# PCB.net
KiCad netlist of a schematic drawn in Altium Designer
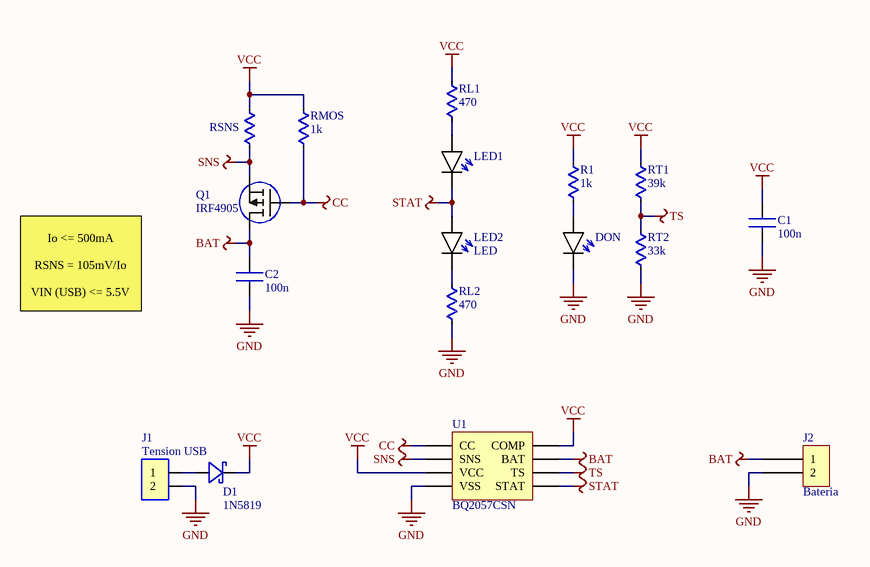
[diagram p0: PCB.SchDoc]

(export (version "E")
  (design (tool "Eeschema 10.0.6"))
  (components
    (comp (ref "C1")
      (value "100n")
      (footprint "CAP-CER")
      (fields (field (name "Comment") "CAP-CER"))
      (libsource (lib "AltiumLibrary") (part "CAP-CER"))
    )
    (comp (ref "C2")
      (value "100n")
      (footprint "CAP-CER")
      (fields (field (name "Comment") "CAP-CER"))
      (libsource (lib "AltiumLibrary") (part "CAP-CER"))
    )
    (comp (ref "D1") (value "1N5819") (footprint "DO-41") (libsource (lib "AltiumLibrary") (part "SCHOTTKY")))
    (comp (ref "DON") (value "LED") (footprint "LED-3MM-RED") (libsource (lib "AltiumLibrary") (part "LED")))
    (comp (ref "J1")
      (value "Tension USB")
      (footprint "BLOCK_TERMINAL-2")
      (libsource (lib "AltiumLibrary") (part "2-BLOCK_TERMINAL"))
    )
    (comp (ref "J2")
      (value "Bateria")
      (footprint "HEADER 1x2")
      (libsource (lib "AltiumLibrary") (part "Header 1x2"))
    )
    (comp (ref "LED1")
      (value "LED")
      (footprint "LED-3MM-GREEN")
      (libsource (lib "AltiumLibrary") (part "LED"))
    )
    (comp (ref "LED2") (value "LED") (footprint "LED-3MM-RED") (libsource (lib "AltiumLibrary") (part "LED")))
    (comp (ref "Q1")
      (value "IRF4905")
      (footprint "TO-220")
      (libsource (lib "AltiumLibrary") (part "P-MOSFET"))
    )
    (comp (ref "R1")
      (value "1k")
      (footprint "RES VERTICAL")
      (fields (field (name "Comment") "RES"))
      (libsource (lib "") (part "RES_1"))
    )
    (comp (ref "RL1")
      (value "470")
      (footprint "AXIAL-0.3")
      (fields (field (name "Comment") "RES"))
      (libsource (lib "AltiumLibrary") (part "RES"))
    )
    (comp (ref "RL2")
      (value "470")
      (footprint "RES VERTICAL")
      (fields (field (name "Comment") "RES"))
      (libsource (lib "AltiumLibrary") (part "RES"))
    )
    (comp (ref "RMOS")
      (value "1k")
      (footprint "RES VERTICAL")
      (fields (field (name "Comment") "RES"))
      (libsource (lib "") (part "RES_1"))
    )
    (comp (ref "RSNS")
      (value "RES")
      (footprint "RES VERTICAL")
      (libsource (lib "AltiumLibrary") (part "RES"))
    )
    (comp (ref "RT1")
      (value "39k")
      (footprint "RES VERTICAL")
      (fields (field (name "Comment") "RES"))
      (libsource (lib "") (part "RES_1"))
    )
    (comp (ref "RT2")
      (value "33k")
      (footprint "RES VERTICAL")
      (fields (field (name "Comment") "RES"))
      (libsource (lib "") (part "RES_1"))
    )
    (comp (ref "U1")
      (value "BQ2057CSN")
      (footprint "SOIC-8")
      (libsource (lib "AltiumLibrary") (part "BQ2057"))
    )
  )
  (nets
    (net (code "1") (name "BAT") (class "Default")
      (node (ref "C2") (pin "2") (pintype "passive"))
      (node (ref "J2") (pin "1") (pinfunction "1_1") (pintype "passive"))
      (node (ref "Q1") (pin "D") (pintype "passive"))
      (node (ref "U1") (pin "2") (pinfunction "BAT_2") (pintype "passive"))
    )
    (net (code "2") (name "CC") (class "Default")
      (node (ref "Q1") (pin "G") (pintype "passive"))
      (node (ref "RMOS") (pin "1") (pintype "passive"))
      (node (ref "U1") (pin "7") (pinfunction "CC_7") (pintype "passive"))
    )
    (net (code "3") (name "GND") (class "Default")
      (node (ref "C1") (pin "1") (pintype "passive"))
      (node (ref "C2") (pin "1") (pintype "passive"))
      (node (ref "DON") (pin "K") (pintype "passive"))
      (node (ref "J1") (pin "2") (pinfunction "2_2") (pintype "passive"))
      (node (ref "J2") (pin "2") (pinfunction "2_2") (pintype "passive"))
      (node (ref "RL2") (pin "2") (pintype "passive"))
      (node (ref "RT2") (pin "1") (pintype "passive"))
      (node (ref "U1") (pin "6") (pinfunction "VSS_6") (pintype "passive"))
    )
    (net (code "4") (name "Net-(D1-PadA)") (class "Default")
      (node (ref "D1") (pin "A") (pintype "passive"))
      (node (ref "J1") (pin "1") (pinfunction "1_1") (pintype "passive"))
    )
    (net (code "5") (name "Net-(DON-PadA)") (class "Default")
      (node (ref "DON") (pin "A") (pintype "passive"))
      (node (ref "R1") (pin "1") (pintype "passive"))
    )
    (net (code "6") (name "Net-(LED1-PadA)") (class "Default")
      (node (ref "LED1") (pin "A") (pintype "passive"))
      (node (ref "RL1") (pin "2") (pintype "passive"))
    )
    (net (code "7") (name "Net-(LED2-PadK)") (class "Default")
      (node (ref "LED2") (pin "K") (pintype "passive"))
      (node (ref "RL2") (pin "1") (pintype "passive"))
    )
    (net (code "8") (name "SNS") (class "Default")
      (node (ref "Q1") (pin "S") (pintype "passive"))
      (node (ref "RSNS") (pin "2") (pintype "passive"))
      (node (ref "U1") (pin "1") (pinfunction "SNS_1") (pintype "passive"))
    )
    (net (code "9") (name "STAT") (class "Default")
      (node (ref "LED1") (pin "K") (pintype "passive"))
      (node (ref "LED2") (pin "A") (pintype "passive"))
      (node (ref "U1") (pin "5") (pinfunction "STAT_5") (pintype "passive"))
    )
    (net (code "10") (name "TS") (class "Default")
      (node (ref "RT1") (pin "1") (pintype "passive"))
      (node (ref "RT2") (pin "2") (pintype "passive"))
      (node (ref "U1") (pin "4") (pinfunction "TS_4") (pintype "passive"))
    )
    (net (code "11") (name "VCC") (class "Default")
      (node (ref "C1") (pin "2") (pintype "passive"))
      (node (ref "D1") (pin "K") (pintype "passive"))
      (node (ref "R1") (pin "2") (pintype "passive"))
      (node (ref "RL1") (pin "1") (pintype "passive"))
      (node (ref "RMOS") (pin "2") (pintype "passive"))
      (node (ref "RSNS") (pin "1") (pintype "passive"))
      (node (ref "RT1") (pin "2") (pintype "passive"))
      (node (ref "U1") (pin "3") (pinfunction "VCC_3") (pintype "passive"))
      (node (ref "U1") (pin "8") (pinfunction "COMP_8") (pintype "passive"))
    )
  )
)
